# mpl115a1.net
KiCad netlist of a schematic drawn in Altium Designer
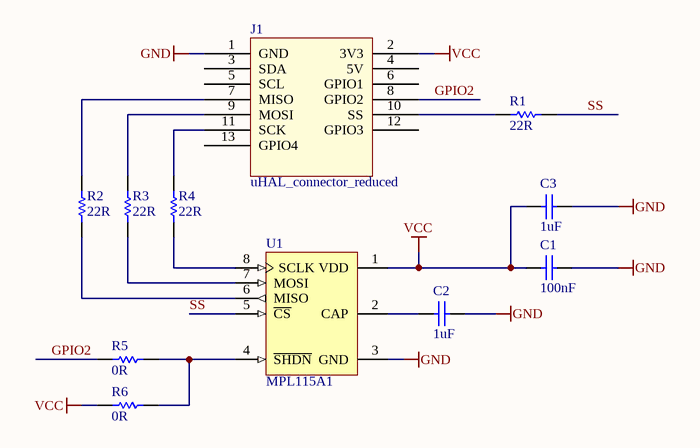
[diagram p0: mpl115a1.SchDoc]

(export (version "E")
  (design (tool "Eeschema 10.0.6"))
  (components
    (comp (ref "C1")
      (value "Murata GCM188R71H104KA57D")
      (footprint "CAPC1608X90X35ML10T15")
      (description "CAP CER 0.1UF 50V 10% X7R 0603")
      (fields (field (name "CAPACITANCE") "100nF"))
      (libsource (lib "CommunityVault") (part "CMP-119667-3"))
    )
    (comp (ref "C2")
      (value "Murata GCM188R71H104KA57D")
      (footprint "CAPC1608X90X35ML10T15")
      (description "CAP CER 0.1UF 50V 10% X7R 0603")
      (fields (field (name "CAPACITANCE") "1uF"))
      (libsource (lib "CommunityVault") (part "CMP-119667-3"))
    )
    (comp (ref "C3")
      (value "Murata GCM188R71H104KA57D")
      (footprint "CAPC1608X90X35ML10T15")
      (description "CAP CER 0.1UF 50V 10% X7R 0603")
      (fields (field (name "CAPACITANCE") "1uF"))
      (libsource (lib "CommunityVault") (part "CMP-119667-3"))
    )
    (comp (ref "J1")
      (value "uHAL_connector_reduced")
      (footprint "PCB-45ncoppm4oopozvqifsq-1")
      (description "connector for uHAL with reduced pin number")
      (libsource (lib "CommunityVault") (part "CMP-2q23h2cwhjlfm8s6r7i8-1"))
    )
    (comp (ref "R1")
      (value "22R")
      (footprint "RESC1608X05N")
      (description "RCA Series 0603 0.1 W 0 O Jumper Surface Mount Thick Film Chip Resistor")
      (fields (field (name "MANUFACTURER PART NUMBER") "RCA06030000ZSEA"))
      (libsource (lib "CommunityVault") (part "CMP-31acf99032f6ee6b-1"))
    )
    (comp (ref "R2")
      (value "22R")
      (footprint "RESC1608X05N")
      (description "RCA Series 0603 0.1 W 0 O Jumper Surface Mount Thick Film Chip Resistor")
      (fields (field (name "MANUFACTURER PART NUMBER") "RCA06030000ZSEA"))
      (libsource (lib "CommunityVault") (part "CMP-31acf99032f6ee6b-1"))
    )
    (comp (ref "R3")
      (value "22R")
      (footprint "RESC1608X05N")
      (description "RCA Series 0603 0.1 W 0 O Jumper Surface Mount Thick Film Chip Resistor")
      (fields (field (name "MANUFACTURER PART NUMBER") "RCA06030000ZSEA"))
      (libsource (lib "CommunityVault") (part "CMP-31acf99032f6ee6b-1"))
    )
    (comp (ref "R4")
      (value "22R")
      (footprint "RESC1608X05N")
      (description "RCA Series 0603 0.1 W 0 O Jumper Surface Mount Thick Film Chip Resistor")
      (fields (field (name "MANUFACTURER PART NUMBER") "RCA06030000ZSEA"))
      (libsource (lib "CommunityVault") (part "CMP-31acf99032f6ee6b-1"))
    )
    (comp (ref "R5")
      (value "0R")
      (footprint "RESC1608X05N")
      (description "RCA Series 0603 0.1 W 0 O Jumper Surface Mount Thick Film Chip Resistor")
      (fields (field (name "MANUFACTURER PART NUMBER") "RCA06030000ZSEA"))
      (libsource (lib "CommunityVault") (part "CMP-31acf99032f6ee6b-1"))
    )
    (comp (ref "R6")
      (value "0R")
      (footprint "RESC1608X05N")
      (description "RCA Series 0603 0.1 W 0 O Jumper Surface Mount Thick Film Chip Resistor")
      (fields (field (name "MANUFACTURER PART NUMBER") "RCA06030000ZSEA"))
      (libsource (lib "CommunityVault") (part "SYM-31acf99032f6ee6b-1"))
    )
    (comp (ref "U1")
      (value "MPL115A1")
      (footprint "FRES-2015-02-A-8_V")
      (description "Pressure Sensor 0V to 0.4V/0V to 0.6V 50kPa to 115kPa Absolute 8-Pin LGA Tray")
      (libsource (lib "CommunityVault") (part "FRES-MPL115A1-LGA-8"))
    )
  )
  (nets
    (net (code "1") (name "/GPIO2") (class "Default")
      (node (ref "J1") (pin "8") (pinfunction "GPIO2_8") (pintype "passive"))
      (node (ref "R5") (pin "2") (pinfunction "2_2") (pintype "passive"))
    )
    (net (code "2") (name "/SS") (class "Default")
      (node (ref "R1") (pin "2") (pinfunction "2_2") (pintype "passive"))
      (node (ref "U1") (pin "5") (pinfunction "~{CS}_5") (pintype "input"))
    )
    (net (code "3") (name "GND") (class "Default")
      (node (ref "C1") (pin "1") (pinfunction "1_1") (pintype "passive"))
      (node (ref "C2") (pin "1") (pinfunction "1_1") (pintype "passive"))
      (node (ref "C3") (pin "1") (pinfunction "1_1") (pintype "passive"))
      (node (ref "J1") (pin "1") (pinfunction "GND_1") (pintype "passive"))
      (node (ref "U1") (pin "3") (pinfunction "GND_3") (pintype "power_in"))
    )
    (net (code "4") (name "Net-(J1-MISO)") (class "Default")
      (node (ref "J1") (pin "7") (pinfunction "MISO_7") (pintype "passive"))
      (node (ref "R2") (pin "1") (pinfunction "1_1") (pintype "passive"))
    )
    (net (code "5") (name "Net-(J1-MOSI)") (class "Default")
      (node (ref "J1") (pin "9") (pinfunction "MOSI_9") (pintype "passive"))
      (node (ref "R3") (pin "1") (pinfunction "1_1") (pintype "passive"))
    )
    (net (code "6") (name "Net-(J1-SCK)") (class "Default")
      (node (ref "J1") (pin "11") (pinfunction "SCK_11") (pintype "passive"))
      (node (ref "R4") (pin "1") (pinfunction "1_1") (pintype "passive"))
    )
    (net (code "7") (name "Net-(J1-SS)") (class "Default")
      (node (ref "J1") (pin "10") (pinfunction "SS_10") (pintype "passive"))
      (node (ref "R1") (pin "1") (pinfunction "1_1") (pintype "passive"))
    )
    (net (code "8") (name "Net-(U1-CAP)") (class "Default")
      (node (ref "C2") (pin "2") (pinfunction "2_2") (pintype "passive"))
      (node (ref "U1") (pin "2") (pinfunction "CAP_2") (pintype "passive"))
    )
    (net (code "9") (name "Net-(U1-MISO)") (class "Default")
      (node (ref "R2") (pin "2") (pinfunction "2_2") (pintype "passive"))
      (node (ref "U1") (pin "6") (pinfunction "MISO_6") (pintype "output"))
    )
    (net (code "10") (name "Net-(U1-MOSI)") (class "Default")
      (node (ref "R3") (pin "2") (pinfunction "2_2") (pintype "passive"))
      (node (ref "U1") (pin "7") (pinfunction "MOSI_7") (pintype "input"))
    )
    (net (code "11") (name "Net-(U1-SCLK)") (class "Default")
      (node (ref "R4") (pin "2") (pinfunction "2_2") (pintype "passive"))
      (node (ref "U1") (pin "8") (pinfunction "SCLK_8") (pintype "input"))
    )
    (net (code "12") (name "Net-(U1-~{SHDN})") (class "Default")
      (node (ref "R5") (pin "1") (pinfunction "1_1") (pintype "passive"))
      (node (ref "R6") (pin "2") (pinfunction "2_2") (pintype "passive"))
      (node (ref "U1") (pin "4") (pinfunction "~{SHDN}_4") (pintype "input"))
    )
    (net (code "13") (name "VCC") (class "Default")
      (node (ref "C1") (pin "2") (pinfunction "2_2") (pintype "passive"))
      (node (ref "C3") (pin "2") (pinfunction "2_2") (pintype "passive"))
      (node (ref "J1") (pin "2") (pinfunction "3V3_2") (pintype "passive"))
      (node (ref "R6") (pin "1") (pinfunction "1_1") (pintype "passive"))
      (node (ref "U1") (pin "1") (pinfunction "VDD_1") (pintype "power_in"))
    )
    (net (code "14") (name "unconnected-(J1-5V-Pad4)") (class "Default")
      (node (ref "J1") (pin "4") (pinfunction "5V_4") (pintype "passive"))
    )
    (net (code "15") (name "unconnected-(J1-GPIO1-Pad6)") (class "Default")
      (node (ref "J1") (pin "6") (pinfunction "GPIO1_6") (pintype "passive"))
    )
    (net (code "16") (name "unconnected-(J1-GPIO3-Pad12)") (class "Default")
      (node (ref "J1") (pin "12") (pinfunction "GPIO3_12") (pintype "passive"))
    )
    (net (code "17") (name "unconnected-(J1-GPIO4-Pad13)") (class "Default")
      (node (ref "J1") (pin "13") (pinfunction "GPIO4_13") (pintype "passive"))
    )
    (net (code "18") (name "unconnected-(J1-SCL-Pad5)") (class "Default")
      (node (ref "J1") (pin "5") (pinfunction "SCL_5") (pintype "passive"))
    )
    (net (code "19") (name "unconnected-(J1-SDA-Pad3)") (class "Default")
      (node (ref "J1") (pin "3") (pinfunction "SDA_3") (pintype "passive"))
    )
  )
)
